# PDB.net
KiCad netlist of a schematic drawn in Altium Designer
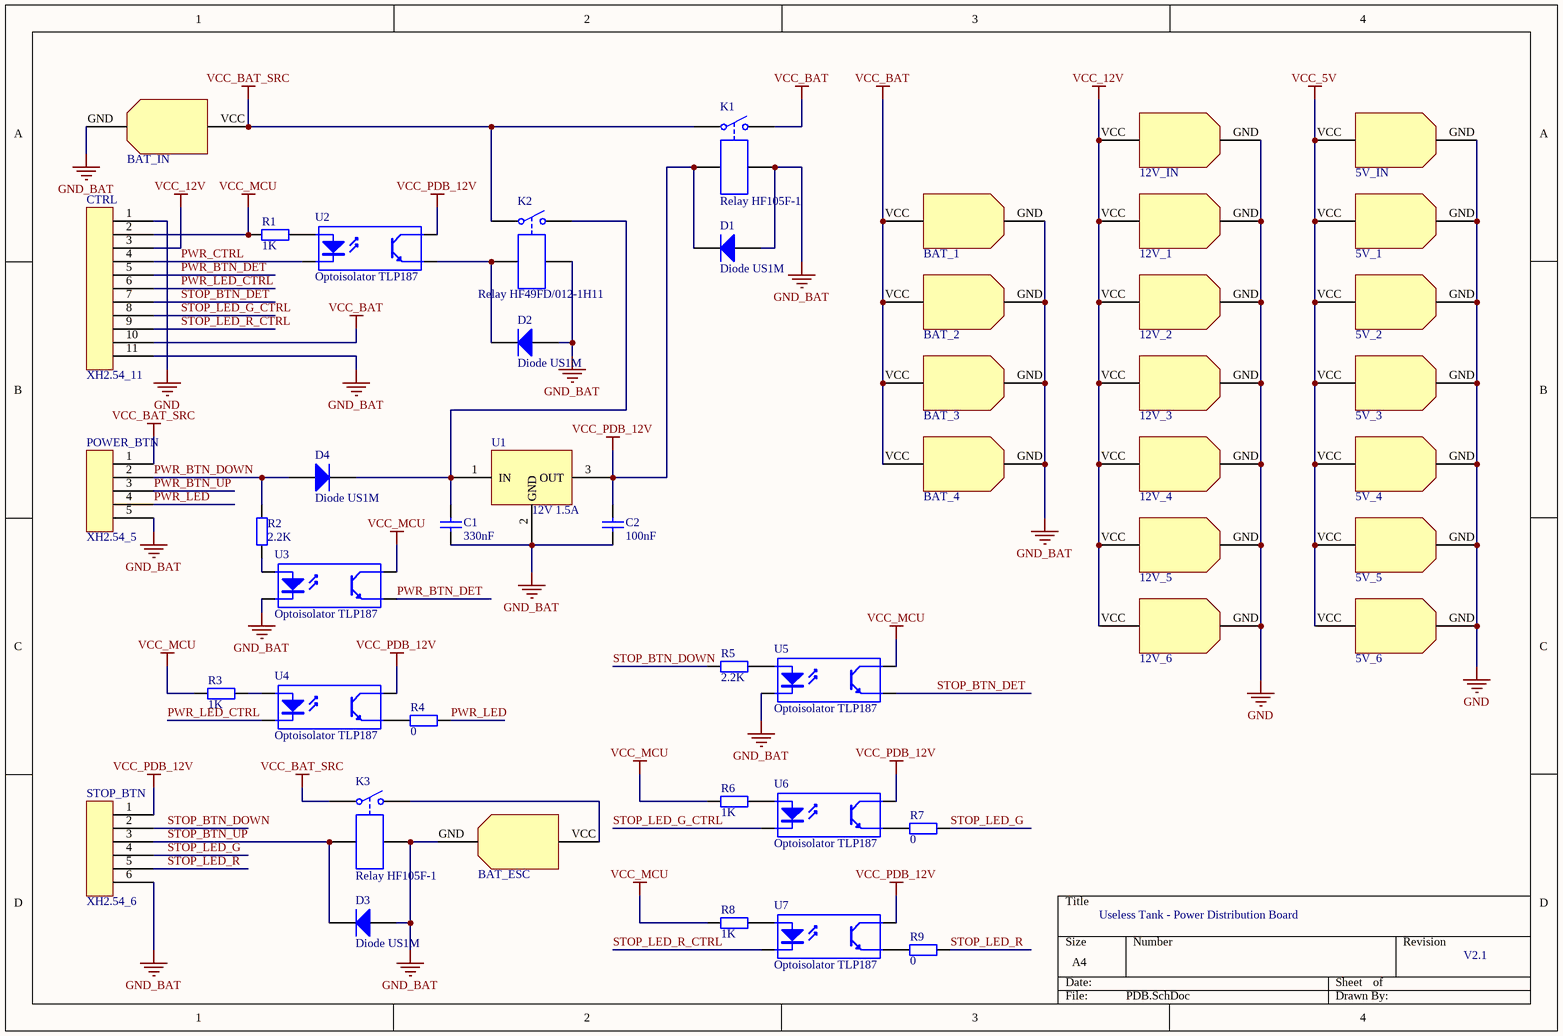
[diagram p0: PDB.SchDoc]

(export (version "E")
  (design (tool "Eeschema 10.0.6"))
  (components
    (comp (ref "5V_1")
      (value "XT30/60/90")
      (footprint "XT30UPB-F")
      (libsource (lib "Connector") (part "XT30/60/90"))
    )
    (comp (ref "5V_2")
      (value "XT30/60/90")
      (footprint "XT30UPB-F")
      (libsource (lib "Connector") (part "XT30/60/90"))
    )
    (comp (ref "5V_3")
      (value "XT30/60/90")
      (footprint "XT30UPB-F")
      (libsource (lib "Connector") (part "XT30/60/90"))
    )
    (comp (ref "5V_4")
      (value "XT30/60/90")
      (footprint "XT30UPB-F")
      (libsource (lib "Connector") (part "XT30/60/90"))
    )
    (comp (ref "5V_5")
      (value "XT30/60/90")
      (footprint "XT30UPB-F")
      (libsource (lib "Connector") (part "XT30/60/90"))
    )
    (comp (ref "5V_6")
      (value "XT30/60/90")
      (footprint "XT30UPB-F")
      (libsource (lib "Connector") (part "XT30/60/90"))
    )
    (comp (ref "5V_IN")
      (value "XT30/60/90")
      (footprint "XT60PB-M")
      (libsource (lib "Connector") (part "XT30/60/90"))
    )
    (comp (ref "12V_1")
      (value "XT30/60/90")
      (footprint "XT60PB-F")
      (libsource (lib "Connector") (part "XT30/60/90"))
    )
    (comp (ref "12V_2")
      (value "XT30/60/90")
      (footprint "XT30UPB-F")
      (libsource (lib "Connector") (part "XT30/60/90"))
    )
    (comp (ref "12V_3")
      (value "XT30/60/90")
      (footprint "XT30UPB-F")
      (libsource (lib "Connector") (part "XT30/60/90"))
    )
    (comp (ref "12V_4")
      (value "XT30/60/90")
      (footprint "XT30UPB-F")
      (libsource (lib "Connector") (part "XT30/60/90"))
    )
    (comp (ref "12V_5")
      (value "XT30/60/90")
      (footprint "XT30UPB-F")
      (libsource (lib "Connector") (part "XT30/60/90"))
    )
    (comp (ref "12V_6")
      (value "XT30/60/90")
      (footprint "XT30UPB-F")
      (libsource (lib "Connector") (part "XT30/60/90"))
    )
    (comp (ref "12V_IN")
      (value "XT30/60/90")
      (footprint "XT60PB-M")
      (libsource (lib "Connector") (part "XT30/60/90"))
    )
    (comp (ref "BAT_1")
      (value "XT30/60/90")
      (footprint "XT60PB-F")
      (libsource (lib "Connector") (part "XT30/60/90"))
    )
    (comp (ref "BAT_2")
      (value "XT30/60/90")
      (footprint "XT60PB-F")
      (libsource (lib "Connector") (part "XT30/60/90"))
    )
    (comp (ref "BAT_3")
      (value "XT30/60/90")
      (footprint "XT30UPB-F")
      (libsource (lib "Connector") (part "XT30/60/90"))
    )
    (comp (ref "BAT_4")
      (value "XT30/60/90")
      (footprint "XT30UPB-F")
      (libsource (lib "Connector") (part "XT30/60/90"))
    )
    (comp (ref "BAT_ESC")
      (value "XT30/60/90")
      (footprint "XT60PB-F")
      (libsource (lib "Connector") (part "XT30/60/90"))
    )
    (comp (ref "BAT_IN")
      (value "XT30/60/90")
      (footprint "XT60PB-M")
      (libsource (lib "Connector") (part "XT30/60/90"))
    )
    (comp (ref "C1")
      (value "330nF")
      (footprint "CAP0805_M")
      (description "Capacitor")
      (fields (field (name "Comment") "Cap") (field (name "PUBLISHER") "Altium Limited"))
      (libsource (lib "Miscellaneous") (part "Cap"))
    )
    (comp (ref "C2")
      (value "100nF")
      (footprint "CAP0805_M")
      (description "Capacitor")
      (fields (field (name "Comment") "Cap") (field (name "PUBLISHER") "Altium Limited"))
      (libsource (lib "Miscellaneous") (part "Cap"))
    )
    (comp (ref "CTRL")
      (value "XH2.54_11")
      (footprint "XH_TH_TOP_11")
      (libsource (lib "Connector") (part "XH2.54_11"))
    )
    (comp (ref "D1")
      (value "Diode US1M")
      (footprint "DO-214AC")
      (description "High Conductance Fast Diode")
      (fields (field (name "PUBLISHER") "Altium Limited"))
      (libsource (lib "Miscellaneous") (part "Diode US1M"))
    )
    (comp (ref "D2")
      (value "Diode US1M")
      (footprint "DO-214AC")
      (description "High Conductance Fast Diode")
      (fields (field (name "PUBLISHER") "Altium Limited"))
      (libsource (lib "Miscellaneous") (part "Diode US1M"))
    )
    (comp (ref "D3")
      (value "Diode US1M")
      (footprint "DO-214AC")
      (description "High Conductance Fast Diode")
      (fields (field (name "PUBLISHER") "Altium Limited"))
      (libsource (lib "Miscellaneous") (part "Diode US1M"))
    )
    (comp (ref "D4")
      (value "Diode US1M")
      (footprint "DO-214AC")
      (description "High Conductance Fast Diode")
      (fields (field (name "PUBLISHER") "Altium Limited"))
      (libsource (lib "Miscellaneous") (part "Diode US1M"))
    )
    (comp (ref "K1")
      (value "Relay HF105F-1")
      (footprint "HF105F-1")
      (description "30A Single-Pole Single-Throw Relay")
      (fields (field (name "PUBLISHER") "Altium Limited"))
      (libsource (lib "Miscellaneous") (part "Relay HF105F-1"))
    )
    (comp (ref "K2")
      (value "Relay HF49FD/012-1H11")
      (footprint "HF49FD/xxx-1Hx1")
      (description "5A Single-Pole Single-Throw Relay")
      (fields (field (name "PUBLISHER") "Altium Limited"))
      (libsource (lib "Miscellaneous") (part "Relay HF49FD/012-1H11"))
    )
    (comp (ref "K3")
      (value "Relay HF105F-1")
      (footprint "HF105F-1")
      (description "30A Single-Pole Single-Throw Relay")
      (fields (field (name "PUBLISHER") "Altium Limited"))
      (libsource (lib "Miscellaneous") (part "Relay HF105F-1"))
    )
    (comp (ref "POWER_BTN")
      (value "XH2.54_5")
      (footprint "XH_TH_TOP_5")
      (libsource (lib "Connector") (part "XH2.54_5"))
    )
    (comp (ref "R1")
      (value "1K")
      (footprint "RES0805_M")
      (description "Resistor")
      (fields (field (name "Comment") "Res2") (field (name "PUBLISHER") "Altium Limited"))
      (libsource (lib "Miscellaneous") (part "Res2"))
    )
    (comp (ref "R2")
      (value "2.2K")
      (footprint "RES0805_M")
      (description "Resistor")
      (fields (field (name "Comment") "Res2") (field (name "PUBLISHER") "Altium Limited"))
      (libsource (lib "") (part "Res2_2"))
    )
    (comp (ref "R3")
      (value "1K")
      (footprint "RES0805_M")
      (description "Resistor")
      (fields (field (name "Comment") "Res2") (field (name "PUBLISHER") "Altium Limited"))
      (libsource (lib "Miscellaneous") (part "Res2"))
    )
    (comp (ref "R4")
      (value "0")
      (footprint "RES1206_M")
      (description "Resistor")
      (fields (field (name "Comment") "Res2") (field (name "PUBLISHER") "Altium Limited"))
      (libsource (lib "Miscellaneous") (part "Res2"))
    )
    (comp (ref "R5")
      (value "2.2K")
      (footprint "RES0805_M")
      (description "Resistor")
      (fields (field (name "Comment") "Res2") (field (name "PUBLISHER") "Altium Limited"))
      (libsource (lib "Miscellaneous") (part "Res2"))
    )
    (comp (ref "R6")
      (value "1K")
      (footprint "RES0805_M")
      (description "Resistor")
      (fields (field (name "Comment") "Res2") (field (name "PUBLISHER") "Altium Limited"))
      (libsource (lib "Miscellaneous") (part "Res2"))
    )
    (comp (ref "R7")
      (value "0")
      (footprint "RES1206_M")
      (description "Resistor")
      (fields (field (name "Comment") "Res2") (field (name "PUBLISHER") "Altium Limited"))
      (libsource (lib "") (part "Res2_1"))
    )
    (comp (ref "R8")
      (value "1K")
      (footprint "RES0805_M")
      (description "Resistor")
      (fields (field (name "Comment") "Res2") (field (name "PUBLISHER") "Altium Limited"))
      (libsource (lib "Miscellaneous") (part "Res2"))
    )
    (comp (ref "R9")
      (value "0")
      (footprint "RES1206_M")
      (description "Resistor")
      (fields (field (name "Comment") "Res2") (field (name "PUBLISHER") "Altium Limited"))
      (libsource (lib "Miscellaneous") (part "Res2"))
    )
    (comp (ref "STOP_BTN")
      (value "XH2.54_6")
      (footprint "XH_TH_TOP_6")
      (libsource (lib "Connector") (part "XH2.54_6"))
    )
    (comp (ref "U1")
      (value "12V 1.5A")
      (footprint "CJ7812_TO-252-2L")
      (description "Voltage Regulator 12V 1.5A")
      (libsource (lib "Miscellaneous") (part "CJ7812"))
    )
    (comp (ref "U2")
      (value "Optoisolator TLP187")
      (footprint "TLP187")
      (description "4-Pin Phototransistor Optocoupler")
      (fields (field (name "PUBLISHER") "Altium Limited"))
      (libsource (lib "Miscellaneous") (part "Optoisolator TLP187"))
    )
    (comp (ref "U3")
      (value "Optoisolator TLP187")
      (footprint "TLP187")
      (description "4-Pin Phototransistor Optocoupler")
      (fields (field (name "PUBLISHER") "Altium Limited"))
      (libsource (lib "Miscellaneous") (part "Optoisolator TLP187"))
    )
    (comp (ref "U4")
      (value "Optoisolator TLP187")
      (footprint "TLP187")
      (description "4-Pin Phototransistor Optocoupler")
      (fields (field (name "PUBLISHER") "Altium Limited"))
      (libsource (lib "Miscellaneous") (part "Optoisolator TLP187"))
    )
    (comp (ref "U5")
      (value "Optoisolator TLP187")
      (footprint "TLP187")
      (description "4-Pin Phototransistor Optocoupler")
      (fields (field (name "PUBLISHER") "Altium Limited"))
      (libsource (lib "Miscellaneous") (part "Optoisolator TLP187"))
    )
    (comp (ref "U6")
      (value "Optoisolator TLP187")
      (footprint "TLP187")
      (description "4-Pin Phototransistor Optocoupler")
      (fields (field (name "PUBLISHER") "Altium Limited"))
      (libsource (lib "Miscellaneous") (part "Optoisolator TLP187"))
    )
    (comp (ref "U7")
      (value "Optoisolator TLP187")
      (footprint "TLP187")
      (description "4-Pin Phototransistor Optocoupler")
      (fields (field (name "PUBLISHER") "Altium Limited"))
      (libsource (lib "Miscellaneous") (part "Optoisolator TLP187"))
    )
  )
  (nets
    (net (code "1") (name "/PWR_BTN_DET") (class "Default")
      (node (ref "CTRL") (pin "5") (pinfunction "5_5") (pintype "passive"))
      (node (ref "U3") (pin "3") (pinfunction "E_3") (pintype "passive"))
    )
    (net (code "2") (name "/PWR_BTN_DOWN") (class "Default")
      (node (ref "D4") (pin "2") (pinfunction "A_2") (pintype "passive"))
      (node (ref "POWER_BTN") (pin "2") (pinfunction "2_2") (pintype "passive"))
      (node (ref "R2") (pin "2") (pinfunction "2_2") (pintype "passive"))
    )
    (net (code "3") (name "/PWR_BTN_UP") (class "Default")
      (node (ref "POWER_BTN") (pin "3") (pinfunction "3_3") (pintype "passive"))
    )
    (net (code "4") (name "/PWR_CTRL") (class "Default")
      (node (ref "CTRL") (pin "4") (pinfunction "4_4") (pintype "passive"))
      (node (ref "U2") (pin "2") (pinfunction "K_2") (pintype "passive"))
    )
    (net (code "5") (name "/PWR_LED") (class "Default")
      (node (ref "POWER_BTN") (pin "4") (pinfunction "4_4") (pintype "passive"))
      (node (ref "R4") (pin "2") (pinfunction "2_2") (pintype "passive"))
    )
    (net (code "6") (name "/PWR_LED_CTRL") (class "Default")
      (node (ref "CTRL") (pin "6") (pinfunction "6_6") (pintype "passive"))
      (node (ref "U4") (pin "2") (pinfunction "K_2") (pintype "passive"))
    )
    (net (code "7") (name "/STOP_BTN_DET") (class "Default")
      (node (ref "CTRL") (pin "7") (pinfunction "7_7") (pintype "passive"))
      (node (ref "U5") (pin "3") (pinfunction "E_3") (pintype "passive"))
    )
    (net (code "8") (name "/STOP_BTN_DOWN") (class "Default")
      (node (ref "R5") (pin "1") (pinfunction "1_1") (pintype "passive"))
      (node (ref "STOP_BTN") (pin "2") (pinfunction "2_2") (pintype "passive"))
    )
    (net (code "9") (name "/STOP_BTN_UP") (class "Default")
      (node (ref "D3") (pin "1") (pinfunction "K_1") (pintype "passive"))
      (node (ref "K3") (pin "3") (pinfunction "3_3") (pintype "passive"))
      (node (ref "STOP_BTN") (pin "3") (pinfunction "3_3") (pintype "passive"))
    )
    (net (code "10") (name "/STOP_LED_G") (class "Default")
      (node (ref "R7") (pin "1") (pinfunction "1_1") (pintype "passive"))
      (node (ref "STOP_BTN") (pin "4") (pinfunction "4_4") (pintype "passive"))
    )
    (net (code "11") (name "/STOP_LED_G_CTRL") (class "Default")
      (node (ref "CTRL") (pin "8") (pinfunction "8_8") (pintype "passive"))
      (node (ref "U6") (pin "2") (pinfunction "K_2") (pintype "passive"))
    )
    (net (code "12") (name "/STOP_LED_R") (class "Default")
      (node (ref "R9") (pin "2") (pinfunction "2_2") (pintype "passive"))
      (node (ref "STOP_BTN") (pin "5") (pinfunction "5_5") (pintype "passive"))
    )
    (net (code "13") (name "/STOP_LED_R_CTRL") (class "Default")
      (node (ref "CTRL") (pin "9") (pinfunction "9_9") (pintype "passive"))
      (node (ref "U7") (pin "2") (pinfunction "K_2") (pintype "passive"))
    )
    (net (code "14") (name "GND") (class "Default")
      (node (ref "12V_1") (pin "GND") (pinfunction "GND_GND") (pintype "power_in"))
      (node (ref "12V_2") (pin "GND") (pinfunction "GND_GND") (pintype "power_in"))
      (node (ref "12V_3") (pin "GND") (pinfunction "GND_GND") (pintype "power_in"))
      (node (ref "12V_4") (pin "GND") (pinfunction "GND_GND") (pintype "power_in"))
      (node (ref "12V_5") (pin "GND") (pinfunction "GND_GND") (pintype "power_in"))
      (node (ref "12V_6") (pin "GND") (pinfunction "GND_GND") (pintype "power_in"))
      (node (ref "12V_IN") (pin "GND") (pinfunction "GND_GND") (pintype "power_in"))
      (node (ref "5V_1") (pin "GND") (pinfunction "GND_GND") (pintype "power_in"))
      (node (ref "5V_2") (pin "GND") (pinfunction "GND_GND") (pintype "power_in"))
      (node (ref "5V_3") (pin "GND") (pinfunction "GND_GND") (pintype "power_in"))
      (node (ref "5V_4") (pin "GND") (pinfunction "GND_GND") (pintype "power_in"))
      (node (ref "5V_5") (pin "GND") (pinfunction "GND_GND") (pintype "power_in"))
      (node (ref "5V_6") (pin "GND") (pinfunction "GND_GND") (pintype "power_in"))
      (node (ref "5V_IN") (pin "GND") (pinfunction "GND_GND") (pintype "power_in"))
      (node (ref "CTRL") (pin "1") (pinfunction "1_1") (pintype "passive"))
    )
    (net (code "15") (name "GND_BAT") (class "Default")
      (node (ref "BAT_1") (pin "GND") (pinfunction "GND_GND") (pintype "power_in"))
      (node (ref "BAT_2") (pin "GND") (pinfunction "GND_GND") (pintype "power_in"))
      (node (ref "BAT_3") (pin "GND") (pinfunction "GND_GND") (pintype "power_in"))
      (node (ref "BAT_4") (pin "GND") (pinfunction "GND_GND") (pintype "power_in"))
      (node (ref "BAT_ESC") (pin "GND") (pinfunction "GND_GND") (pintype "power_in"))
      (node (ref "BAT_IN") (pin "GND") (pinfunction "GND_GND") (pintype "power_in"))
      (node (ref "C1") (pin "1") (pinfunction "1_1") (pintype "passive"))
      (node (ref "C2") (pin "1") (pinfunction "1_1") (pintype "passive"))
      (node (ref "CTRL") (pin "11") (pinfunction "11_11") (pintype "passive"))
      (node (ref "D1") (pin "2") (pinfunction "A_2") (pintype "passive"))
      (node (ref "D2") (pin "2") (pinfunction "A_2") (pintype "passive"))
      (node (ref "D3") (pin "2") (pinfunction "A_2") (pintype "passive"))
      (node (ref "K1") (pin "4") (pinfunction "4_4") (pintype "passive"))
      (node (ref "K2") (pin "4") (pinfunction "4_4") (pintype "passive"))
      (node (ref "K3") (pin "4") (pinfunction "4_4") (pintype "passive"))
      (node (ref "POWER_BTN") (pin "5") (pinfunction "5_5") (pintype "passive"))
      (node (ref "STOP_BTN") (pin "6") (pinfunction "6_6") (pintype "passive"))
      (node (ref "U1") (pin "2") (pinfunction "GND_2") (pintype "passive"))
      (node (ref "U3") (pin "2") (pinfunction "K_2") (pintype "passive"))
      (node (ref "U5") (pin "2") (pinfunction "K_2") (pintype "passive"))
    )
    (net (code "16") (name "Net-(BAT_ESC-PadVCC)") (class "Default")
      (node (ref "BAT_ESC") (pin "VCC") (pinfunction "VCC_VCC") (pintype "power_in"))
      (node (ref "K3") (pin "2") (pinfunction "2_2") (pintype "passive"))
    )
    (net (code "17") (name "Net-(D2-K)") (class "Default")
      (node (ref "D2") (pin "1") (pinfunction "K_1") (pintype "passive"))
      (node (ref "K2") (pin "3") (pinfunction "3_3") (pintype "passive"))
      (node (ref "U2") (pin "3") (pinfunction "E_3") (pintype "passive"))
    )
    (net (code "18") (name "Net-(D4-K)") (class "Default")
      (node (ref "C1") (pin "2") (pinfunction "2_2") (pintype "passive"))
      (node (ref "D4") (pin "1") (pinfunction "K_1") (pintype "passive"))
      (node (ref "K2") (pin "2") (pinfunction "2_2") (pintype "passive"))
      (node (ref "U1") (pin "1") (pinfunction "IN_1") (pintype "passive"))
    )
    (net (code "19") (name "Net-(U2-A)") (class "Default")
      (node (ref "R1") (pin "2") (pinfunction "2_2") (pintype "passive"))
      (node (ref "U2") (pin "1") (pinfunction "A_1") (pintype "passive"))
    )
    (net (code "20") (name "Net-(U3-A)") (class "Default")
      (node (ref "R2") (pin "1") (pinfunction "1_1") (pintype "passive"))
      (node (ref "U3") (pin "1") (pinfunction "A_1") (pintype "passive"))
    )
    (net (code "21") (name "Net-(U4-A)") (class "Default")
      (node (ref "R3") (pin "2") (pinfunction "2_2") (pintype "passive"))
      (node (ref "U4") (pin "1") (pinfunction "A_1") (pintype "passive"))
    )
    (net (code "22") (name "Net-(U4-E)") (class "Default")
      (node (ref "R4") (pin "1") (pinfunction "1_1") (pintype "passive"))
      (node (ref "U4") (pin "3") (pinfunction "E_3") (pintype "passive"))
    )
    (net (code "23") (name "Net-(U5-A)") (class "Default")
      (node (ref "R5") (pin "2") (pinfunction "2_2") (pintype "passive"))
      (node (ref "U5") (pin "1") (pinfunction "A_1") (pintype "passive"))
    )
    (net (code "24") (name "Net-(U6-A)") (class "Default")
      (node (ref "R6") (pin "2") (pinfunction "2_2") (pintype "passive"))
      (node (ref "U6") (pin "1") (pinfunction "A_1") (pintype "passive"))
    )
    (net (code "25") (name "Net-(U6-E)") (class "Default")
      (node (ref "R7") (pin "2") (pinfunction "2_2") (pintype "passive"))
      (node (ref "U6") (pin "3") (pinfunction "E_3") (pintype "passive"))
    )
    (net (code "26") (name "Net-(U7-A)") (class "Default")
      (node (ref "R8") (pin "2") (pinfunction "2_2") (pintype "passive"))
      (node (ref "U7") (pin "1") (pinfunction "A_1") (pintype "passive"))
    )
    (net (code "27") (name "Net-(U7-E)") (class "Default")
      (node (ref "R9") (pin "1") (pinfunction "1_1") (pintype "passive"))
      (node (ref "U7") (pin "3") (pinfunction "E_3") (pintype "passive"))
    )
    (net (code "28") (name "VCC_5V") (class "Default")
      (node (ref "5V_1") (pin "VCC") (pinfunction "VCC_VCC") (pintype "power_in"))
      (node (ref "5V_2") (pin "VCC") (pinfunction "VCC_VCC") (pintype "power_in"))
      (node (ref "5V_3") (pin "VCC") (pinfunction "VCC_VCC") (pintype "power_in"))
      (node (ref "5V_4") (pin "VCC") (pinfunction "VCC_VCC") (pintype "power_in"))
      (node (ref "5V_5") (pin "VCC") (pinfunction "VCC_VCC") (pintype "power_in"))
      (node (ref "5V_6") (pin "VCC") (pinfunction "VCC_VCC") (pintype "power_in"))
      (node (ref "5V_IN") (pin "VCC") (pinfunction "VCC_VCC") (pintype "power_in"))
    )
    (net (code "29") (name "VCC_12V") (class "Default")
      (node (ref "12V_1") (pin "VCC") (pinfunction "VCC_VCC") (pintype "power_in"))
      (node (ref "12V_2") (pin "VCC") (pinfunction "VCC_VCC") (pintype "power_in"))
      (node (ref "12V_3") (pin "VCC") (pinfunction "VCC_VCC") (pintype "power_in"))
      (node (ref "12V_4") (pin "VCC") (pinfunction "VCC_VCC") (pintype "power_in"))
      (node (ref "12V_5") (pin "VCC") (pinfunction "VCC_VCC") (pintype "power_in"))
      (node (ref "12V_6") (pin "VCC") (pinfunction "VCC_VCC") (pintype "power_in"))
      (node (ref "12V_IN") (pin "VCC") (pinfunction "VCC_VCC") (pintype "power_in"))
      (node (ref "CTRL") (pin "3") (pinfunction "3_3") (pintype "passive"))
    )
    (net (code "30") (name "VCC_BAT") (class "Default")
      (node (ref "BAT_1") (pin "VCC") (pinfunction "VCC_VCC") (pintype "power_in"))
      (node (ref "BAT_2") (pin "VCC") (pinfunction "VCC_VCC") (pintype "power_in"))
      (node (ref "BAT_3") (pin "VCC") (pinfunction "VCC_VCC") (pintype "power_in"))
      (node (ref "BAT_4") (pin "VCC") (pinfunction "VCC_VCC") (pintype "power_in"))
      (node (ref "CTRL") (pin "10") (pinfunction "10_10") (pintype "passive"))
      (node (ref "K1") (pin "2") (pinfunction "2_2") (pintype "passive"))
    )
    (net (code "31") (name "VCC_BAT_SRC") (class "Default")
      (node (ref "BAT_IN") (pin "VCC") (pinfunction "VCC_VCC") (pintype "power_in"))
      (node (ref "K1") (pin "1") (pinfunction "1_1") (pintype "passive"))
      (node (ref "K2") (pin "1") (pinfunction "1_1") (pintype "passive"))
      (node (ref "K3") (pin "1") (pinfunction "1_1") (pintype "passive"))
      (node (ref "POWER_BTN") (pin "1") (pinfunction "1_1") (pintype "passive"))
    )
    (net (code "32") (name "VCC_MCU") (class "Default")
      (node (ref "CTRL") (pin "2") (pinfunction "2_2") (pintype "passive"))
      (node (ref "R1") (pin "1") (pinfunction "1_1") (pintype "passive"))
      (node (ref "R3") (pin "1") (pinfunction "1_1") (pintype "passive"))
      (node (ref "R6") (pin "1") (pinfunction "1_1") (pintype "passive"))
      (node (ref "R8") (pin "1") (pinfunction "1_1") (pintype "passive"))
      (node (ref "U3") (pin "4") (pinfunction "C_4") (pintype "passive"))
      (node (ref "U5") (pin "4") (pinfunction "C_4") (pintype "passive"))
    )
    (net (code "33") (name "VCC_PDB_12V") (class "Default")
      (node (ref "C2") (pin "2") (pinfunction "2_2") (pintype "passive"))
      (node (ref "D1") (pin "1") (pinfunction "K_1") (pintype "passive"))
      (node (ref "K1") (pin "3") (pinfunction "3_3") (pintype "passive"))
      (node (ref "STOP_BTN") (pin "1") (pinfunction "1_1") (pintype "passive"))
      (node (ref "U1") (pin "3") (pinfunction "OUT_3") (pintype "passive"))
      (node (ref "U2") (pin "4") (pinfunction "C_4") (pintype "passive"))
      (node (ref "U4") (pin "4") (pinfunction "C_4") (pintype "passive"))
      (node (ref "U6") (pin "4") (pinfunction "C_4") (pintype "passive"))
      (node (ref "U7") (pin "4") (pinfunction "C_4") (pintype "passive"))
    )
  )
)
